# EMS_esp32_wifi_v2_4.net
KiCad netlist of a schematic drawn in EAGLE
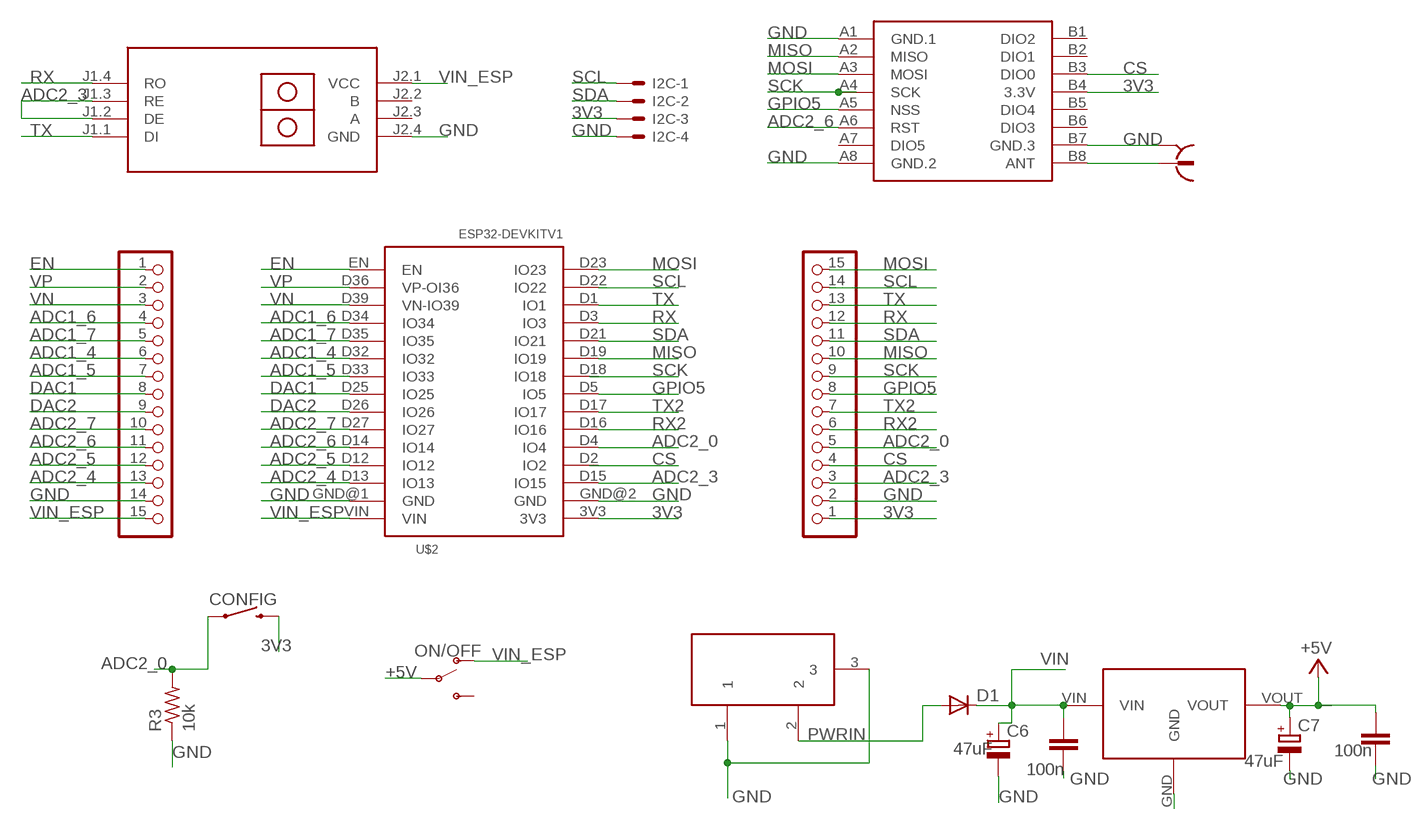
[diagram p0: schematic, sheet 1]

(export (version "E")
  (design (tool "Eeschema 10.0.6"))
  (components
    (comp (ref "C5")
      (value "100n")
      (footprint "eagle-import:C1206")
      (libsource (lib "eagle-import") (part "C-EUC1206"))
    )
    (comp (ref "C6")
      (value "47uF")
      (footprint "eagle-import:PANASONIC_D")
      (libsource (lib "eagle-import") (part "CPOL-EUD"))
    )
    (comp (ref "C7")
      (value "47uF")
      (footprint "eagle-import:PANASONIC_D")
      (libsource (lib "eagle-import") (part "CPOL-EUD"))
    )
    (comp (ref "C14")
      (value "100n")
      (footprint "eagle-import:C1206")
      (libsource (lib "eagle-import") (part "C-EUC1206"))
    )
    (comp (ref "CONFIG")
      (value "MOMENTARY-SWITCH-SPST-PTH-6.0MM")
      (footprint "eagle-import:TACTILE_SWITCH_PTH_6.0MM")
      (libsource (lib "eagle-import") (part "MOMENTARY-SWITCH-SPST-PTH-6.0MM"))
    )
    (comp (ref "D1")
      (value "DIODE-SMB")
      (footprint "eagle-import:SMB")
      (libsource (lib "eagle-import") (part "DIODE-SMB"))
    )
    (comp (ref "I2C")
      (value "22-23-2041")
      (footprint "eagle-import:22-23-2041")
      (fields (field (name "MF") "MOLEX"))
      (libsource (lib "eagle-import") (part "22-23-2041"))
    )
    (comp (ref "JP1")
      (value "PINHD-1X15")
      (footprint "eagle-import:1X15")
      (libsource (lib "eagle-import") (part "PINHD-1X15"))
    )
    (comp (ref "JP2")
      (value "PINHD-1X15")
      (footprint "eagle-import:1X15")
      (libsource (lib "eagle-import") (part "PINHD-1X15"))
    )
    (comp (ref "ON/OFF")
      (value "SWITCH-SPDT-PTH-11.6X4.0MM")
      (footprint "eagle-import:SWITCH_SPDT_PTH_11.6X4.0MM")
      (libsource (lib "eagle-import") (part "SWITCH-SPDT-PTH-11.6X4.0MM"))
    )
    (comp (ref "R3")
      (value "10k")
      (footprint "eagle-import:0204_7")
      (libsource (lib "eagle-import") (part "R-US_0204/7"))
    )
    (comp (ref "RFM95")
      (value "WIRELESS-LORA-RFM95W#SMD")
      (footprint "eagle-import:WIRELESS-LORA-RFM95W#SMD")
      (libsource (lib "eagle-import") (part "WIRELESS-LORA-RFM95W#SMD"))
    )
    (comp (ref "U$1")
      (value "RS485-TTL-CONVERTER")
      (footprint "eagle-import:RS485-TTL-CONVERTER")
      (libsource (lib "eagle-import") (part "RS485-TTL-CONVERTER"))
    )
    (comp (ref "U$2")
      (value "ESP32DEVKITV1")
      (footprint "eagle-import:ESP32-DEVKITV1")
      (libsource (lib "eagle-import") (part "ESP32DEVKITV1"))
    )
    (comp (ref "U$3")
      (value "SMARTPRJ_POWERSUPPLY_DC21MMX")
      (footprint "eagle-import:SMARTPRJ_POWERSUPPLY_DC-21MM")
      (libsource (lib "eagle-import") (part "SMARTPRJ_POWERSUPPLY_DC21MMX"))
    )
    (comp (ref "U$4")
      (value "7805-TO263_7805")
      (footprint "eagle-import:7805-TO263_TO263")
      (libsource (lib "eagle-import") (part "7805-TO263_7805"))
    )
    (comp (ref "X1")
      (value "734120110")
      (footprint "eagle-import:734120110")
      (libsource (lib "eagle-import") (part "734120110"))
    )
  )
  (nets
    (net (code "1") (name "+5V") (class "Default")
      (node (ref "C14") (pin "2") (pinfunction "2_2") (pintype "passive"))
      (node (ref "C7") (pin "+") (pinfunction "+_+") (pintype "passive"))
      (node (ref "ON/OFF") (pin "2") (pinfunction "P_2") (pintype "passive"))
      (node (ref "U$4") (pin "VOUT") (pinfunction "VOUT_VOUT") (pintype "bidirectional"))
    )
    (net (code "2") (name "/3V3") (class "Default")
      (node (ref "CONFIG") (pin "3") (pinfunction "2_3") (pintype "passive"))
      (node (ref "I2C") (pin "3") (pinfunction "S_3") (pintype "passive"))
      (node (ref "JP2") (pin "1") (pinfunction "1_1") (pintype "passive"))
      (node (ref "RFM95") (pin "B4") (pinfunction "3.3V_B4") (pintype "power_in"))
      (node (ref "U$2") (pin "3V3") (pinfunction "3V3_3V3") (pintype "bidirectional"))
    )
    (net (code "3") (name "/ADC1_4") (class "Default")
      (node (ref "JP1") (pin "6") (pinfunction "6_6") (pintype "passive"))
      (node (ref "U$2") (pin "D32") (pinfunction "IO32_D32") (pintype "bidirectional"))
    )
    (net (code "4") (name "/ADC1_5") (class "Default")
      (node (ref "JP1") (pin "7") (pinfunction "7_7") (pintype "passive"))
      (node (ref "U$2") (pin "D33") (pinfunction "IO33_D33") (pintype "bidirectional"))
    )
    (net (code "5") (name "/ADC1_6") (class "Default")
      (node (ref "JP1") (pin "4") (pinfunction "4_4") (pintype "passive"))
      (node (ref "U$2") (pin "D34") (pinfunction "IO34_D34") (pintype "bidirectional"))
    )
    (net (code "6") (name "/ADC1_7") (class "Default")
      (node (ref "JP1") (pin "5") (pinfunction "5_5") (pintype "passive"))
      (node (ref "U$2") (pin "D35") (pinfunction "IO35_D35") (pintype "bidirectional"))
    )
    (net (code "7") (name "/ADC2_0") (class "Default")
      (node (ref "CONFIG") (pin "1") (pinfunction "1_1") (pintype "passive"))
      (node (ref "JP2") (pin "5") (pinfunction "5_5") (pintype "passive"))
      (node (ref "R3") (pin "2") (pinfunction "2_2") (pintype "passive"))
      (node (ref "U$2") (pin "D4") (pinfunction "IO4_D4") (pintype "bidirectional"))
    )
    (net (code "8") (name "/ADC2_3") (class "Default")
      (node (ref "JP2") (pin "3") (pinfunction "3_3") (pintype "passive"))
      (node (ref "U$1") (pin "J1.2") (pinfunction "DE_J1.2") (pintype "passive"))
      (node (ref "U$1") (pin "J1.3") (pinfunction "RE_J1.3") (pintype "passive"))
      (node (ref "U$2") (pin "D15") (pinfunction "IO15_D15") (pintype "bidirectional"))
    )
    (net (code "9") (name "/ADC2_4") (class "Default")
      (node (ref "JP1") (pin "13") (pinfunction "13_13") (pintype "passive"))
      (node (ref "U$2") (pin "D13") (pinfunction "IO13_D13") (pintype "bidirectional"))
    )
    (net (code "10") (name "/ADC2_5") (class "Default")
      (node (ref "JP1") (pin "12") (pinfunction "12_12") (pintype "passive"))
      (node (ref "U$2") (pin "D12") (pinfunction "IO12_D12") (pintype "bidirectional"))
    )
    (net (code "11") (name "/ADC2_6") (class "Default")
      (node (ref "JP1") (pin "11") (pinfunction "11_11") (pintype "passive"))
      (node (ref "RFM95") (pin "A6") (pinfunction "RST_A6") (pintype "bidirectional"))
      (node (ref "U$2") (pin "D14") (pinfunction "IO14_D14") (pintype "bidirectional"))
    )
    (net (code "12") (name "/ADC2_7") (class "Default")
      (node (ref "JP1") (pin "10") (pinfunction "10_10") (pintype "passive"))
      (node (ref "U$2") (pin "D27") (pinfunction "IO27_D27") (pintype "bidirectional"))
    )
    (net (code "13") (name "/CS") (class "Default")
      (node (ref "JP2") (pin "4") (pinfunction "4_4") (pintype "passive"))
      (node (ref "RFM95") (pin "B3") (pinfunction "DIO0_B3") (pintype "bidirectional"))
      (node (ref "U$2") (pin "D2") (pinfunction "IO2_D2") (pintype "bidirectional"))
    )
    (net (code "14") (name "/DAC1") (class "Default")
      (node (ref "JP1") (pin "8") (pinfunction "8_8") (pintype "passive"))
      (node (ref "U$2") (pin "D25") (pinfunction "IO25_D25") (pintype "bidirectional"))
    )
    (net (code "15") (name "/DAC2") (class "Default")
      (node (ref "JP1") (pin "9") (pinfunction "9_9") (pintype "passive"))
      (node (ref "U$2") (pin "D26") (pinfunction "IO26_D26") (pintype "bidirectional"))
    )
    (net (code "16") (name "/EN") (class "Default")
      (node (ref "JP1") (pin "1") (pinfunction "1_1") (pintype "passive"))
      (node (ref "U$2") (pin "EN") (pinfunction "EN_EN") (pintype "bidirectional"))
    )
    (net (code "17") (name "/GND") (class "Default")
      (node (ref "C14") (pin "1") (pinfunction "1_1") (pintype "passive"))
      (node (ref "C5") (pin "1") (pinfunction "1_1") (pintype "passive"))
      (node (ref "C6") (pin "-") (pinfunction "-_-") (pintype "passive"))
      (node (ref "C7") (pin "-") (pinfunction "-_-") (pintype "passive"))
      (node (ref "I2C") (pin "4") (pinfunction "S_4") (pintype "passive"))
      (node (ref "JP1") (pin "14") (pinfunction "14_14") (pintype "passive"))
      (node (ref "JP2") (pin "2") (pinfunction "2_2") (pintype "passive"))
      (node (ref "R3") (pin "1") (pinfunction "1_1") (pintype "passive"))
      (node (ref "RFM95") (pin "A1") (pinfunction "GND.1_A1") (pintype "power_in"))
      (node (ref "RFM95") (pin "A8") (pinfunction "GND.2_A8") (pintype "power_in"))
      (node (ref "RFM95") (pin "B7") (pinfunction "GND.3_B7") (pintype "power_in"))
      (node (ref "U$1") (pin "J2.4") (pinfunction "GND_J2.4") (pintype "power_in"))
      (node (ref "U$2") (pin "GND@1") (pinfunction "GND_GND@1") (pintype "bidirectional"))
      (node (ref "U$2") (pin "GND@2") (pinfunction "GND_GND@2") (pintype "bidirectional"))
      (node (ref "U$3") (pin "1") (pinfunction "1_1") (pintype "power_in"))
      (node (ref "U$3") (pin "3") (pinfunction "3_3") (pintype "power_in"))
      (node (ref "U$4") (pin "GND") (pinfunction "GND_GND") (pintype "bidirectional"))
      (node (ref "X1") (pin "S@1") (pinfunction "2_S@1") (pintype "passive"))
      (node (ref "X1") (pin "S@2") (pinfunction "2_S@2") (pintype "passive"))
      (node (ref "X1") (pin "S@3") (pinfunction "2_S@3") (pintype "passive"))
    )
    (net (code "18") (name "/GPIO5") (class "Default")
      (node (ref "JP2") (pin "8") (pinfunction "8_8") (pintype "passive"))
      (node (ref "RFM95") (pin "A5") (pinfunction "NSS_A5") (pintype "bidirectional"))
      (node (ref "U$2") (pin "D5") (pinfunction "IO5_D5") (pintype "bidirectional"))
    )
    (net (code "19") (name "/MISO") (class "Default")
      (node (ref "JP2") (pin "10") (pinfunction "10_10") (pintype "passive"))
      (node (ref "RFM95") (pin "A2") (pinfunction "MISO_A2") (pintype "bidirectional"))
      (node (ref "U$2") (pin "D19") (pinfunction "IO19_D19") (pintype "bidirectional"))
    )
    (net (code "20") (name "/MOSI") (class "Default")
      (node (ref "JP2") (pin "15") (pinfunction "15_15") (pintype "passive"))
      (node (ref "RFM95") (pin "A3") (pinfunction "MOSI_A3") (pintype "bidirectional"))
      (node (ref "U$2") (pin "D23") (pinfunction "IO23_D23") (pintype "bidirectional"))
    )
    (net (code "21") (name "/PWRIN") (class "Default")
      (node (ref "D1") (pin "A") (pinfunction "A_A") (pintype "passive"))
      (node (ref "U$3") (pin "2") (pinfunction "2_2") (pintype "power_in"))
    )
    (net (code "22") (name "/RX") (class "Default")
      (node (ref "JP2") (pin "12") (pinfunction "12_12") (pintype "passive"))
      (node (ref "U$1") (pin "J1.4") (pinfunction "RO_J1.4") (pintype "passive"))
      (node (ref "U$2") (pin "D3") (pinfunction "IO3_D3") (pintype "bidirectional"))
    )
    (net (code "23") (name "/RX2") (class "Default")
      (node (ref "JP2") (pin "6") (pinfunction "6_6") (pintype "passive"))
      (node (ref "U$2") (pin "D16") (pinfunction "IO16_D16") (pintype "bidirectional"))
    )
    (net (code "24") (name "/SCK") (class "Default")
      (node (ref "JP2") (pin "9") (pinfunction "9_9") (pintype "passive"))
      (node (ref "RFM95") (pin "A4") (pinfunction "SCK_A4") (pintype "bidirectional"))
      (node (ref "U$2") (pin "D18") (pinfunction "IO18_D18") (pintype "bidirectional"))
    )
    (net (code "25") (name "/SCL") (class "Default")
      (node (ref "I2C") (pin "1") (pinfunction "S_1") (pintype "passive"))
      (node (ref "JP2") (pin "14") (pinfunction "14_14") (pintype "passive"))
      (node (ref "U$2") (pin "D22") (pinfunction "IO22_D22") (pintype "bidirectional"))
    )
    (net (code "26") (name "/SDA") (class "Default")
      (node (ref "I2C") (pin "2") (pinfunction "S_2") (pintype "passive"))
      (node (ref "JP2") (pin "11") (pinfunction "11_11") (pintype "passive"))
      (node (ref "U$2") (pin "D21") (pinfunction "IO21_D21") (pintype "bidirectional"))
    )
    (net (code "27") (name "/TX") (class "Default")
      (node (ref "JP2") (pin "13") (pinfunction "13_13") (pintype "passive"))
      (node (ref "U$1") (pin "J1.1") (pinfunction "DI_J1.1") (pintype "passive"))
      (node (ref "U$2") (pin "D1") (pinfunction "IO1_D1") (pintype "bidirectional"))
    )
    (net (code "28") (name "/TX2") (class "Default")
      (node (ref "JP2") (pin "7") (pinfunction "7_7") (pintype "passive"))
      (node (ref "U$2") (pin "D17") (pinfunction "IO17_D17") (pintype "bidirectional"))
    )
    (net (code "29") (name "/VIN") (class "Default")
      (node (ref "C5") (pin "2") (pinfunction "2_2") (pintype "passive"))
      (node (ref "C6") (pin "+") (pinfunction "+_+") (pintype "passive"))
      (node (ref "D1") (pin "C") (pinfunction "C_C") (pintype "passive"))
      (node (ref "U$4") (pin "VIN") (pinfunction "VIN_VIN") (pintype "bidirectional"))
    )
    (net (code "30") (name "/VIN_ESP") (class "Default")
      (node (ref "JP1") (pin "15") (pinfunction "15_15") (pintype "passive"))
      (node (ref "ON/OFF") (pin "1") (pinfunction "O_1") (pintype "passive"))
      (node (ref "U$1") (pin "J2.1") (pinfunction "VCC_J2.1") (pintype "power_in"))
      (node (ref "U$2") (pin "VIN") (pinfunction "VIN_VIN") (pintype "bidirectional"))
    )
    (net (code "31") (name "/VN") (class "Default")
      (node (ref "JP1") (pin "3") (pinfunction "3_3") (pintype "passive"))
      (node (ref "U$2") (pin "D39") (pinfunction "VN-IO39_D39") (pintype "bidirectional"))
    )
    (net (code "32") (name "/VP") (class "Default")
      (node (ref "JP1") (pin "2") (pinfunction "2_2") (pintype "passive"))
      (node (ref "U$2") (pin "D36") (pinfunction "VP-OI36_D36") (pintype "bidirectional"))
    )
    (net (code "33") (name "Net-(RFM95-ANT)") (class "Default")
      (node (ref "RFM95") (pin "B8") (pinfunction "ANT_B8") (pintype "passive"))
      (node (ref "X1") (pin "1") (pinfunction "1_1") (pintype "passive"))
    )
    (net (code "34") (name "unconnected-(ON/OFF-S-Pad3)") (class "Default")
      (node (ref "ON/OFF") (pin "3") (pinfunction "S_3") (pintype "passive"))
    )
    (net (code "35") (name "unconnected-(RFM95-DIO1-PadB2)") (class "Default")
      (node (ref "RFM95") (pin "B2") (pinfunction "DIO1_B2") (pintype "bidirectional"))
    )
    (net (code "36") (name "unconnected-(RFM95-DIO2-PadB1)") (class "Default")
      (node (ref "RFM95") (pin "B1") (pinfunction "DIO2_B1") (pintype "bidirectional"))
    )
    (net (code "37") (name "unconnected-(RFM95-DIO3-PadB6)") (class "Default")
      (node (ref "RFM95") (pin "B6") (pinfunction "DIO3_B6") (pintype "bidirectional"))
    )
    (net (code "38") (name "unconnected-(RFM95-DIO4-PadB5)") (class "Default")
      (node (ref "RFM95") (pin "B5") (pinfunction "DIO4_B5") (pintype "bidirectional"))
    )
    (net (code "39") (name "unconnected-(RFM95-DIO5-PadA7)") (class "Default")
      (node (ref "RFM95") (pin "A7") (pinfunction "DIO5_A7") (pintype "bidirectional"))
    )
    (net (code "40") (name "unconnected-(U$1-A-PadJ2.3)") (class "Default")
      (node (ref "U$1") (pin "J2.3") (pinfunction "A_J2.3") (pintype "passive"))
    )
    (net (code "41") (name "unconnected-(U$1-B-PadJ2.2)") (class "Default")
      (node (ref "U$1") (pin "J2.2") (pinfunction "B_J2.2") (pintype "passive"))
    )
  )
)
